# Atividade-03.net
KiCad netlist of a schematic drawn in EAGLE
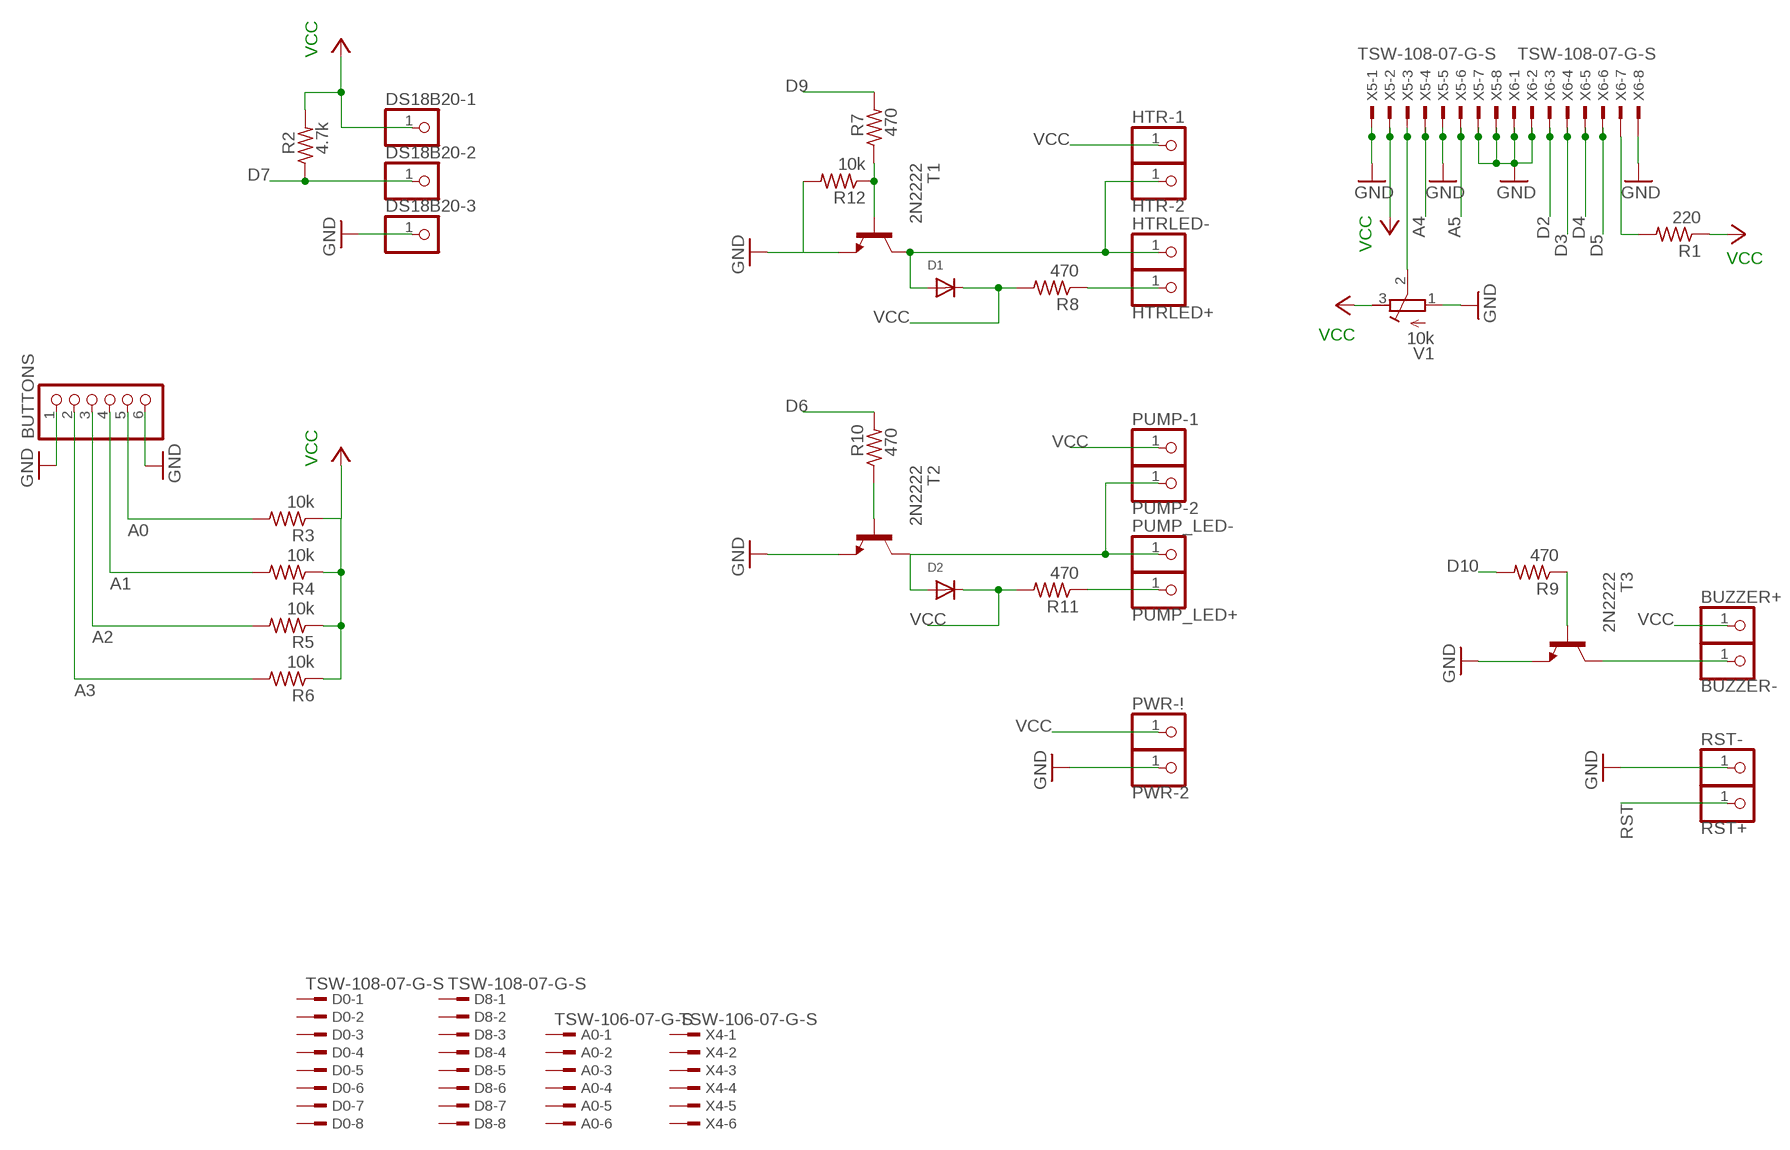
[diagram p0: schematic, sheet 1]

(export (version "E")
  (design (tool "Eeschema 10.0.6"))
  (components
    (comp (ref "A0")
      (value "TSW-106-07-G-S")
      (footprint "eagle-import:TSW-106-XX-G-S")
      (fields (field (name "MF") "Samtec Inc."))
      (libsource (lib "eagle-import") (part "TSW-106--G-S07"))
    )
    (comp (ref "BUTTONS")
      (value "PINHD-1X6")
      (footprint "eagle-import:1X06")
      (libsource (lib "eagle-import") (part "PINHD-1X6"))
    )
    (comp (ref "BUZZER+")
      (value "PINHD-1X1")
      (footprint "eagle-import:1X01")
      (libsource (lib "eagle-import") (part "PINHD-1X1"))
    )
    (comp (ref "BUZZER-")
      (value "PINHD-1X1")
      (footprint "eagle-import:1X01")
      (libsource (lib "eagle-import") (part "PINHD-1X1"))
    )
    (comp (ref "D0")
      (value "TSW-108-07-G-S")
      (footprint "eagle-import:TSW-108-XX-G-S")
      (fields (field (name "MF") "Samtec Inc."))
      (libsource (lib "eagle-import") (part "TSW-108--G-S07"))
    )
    (comp (ref "D1")
      (value "DIODEDO-1N4148")
      (footprint "eagle-import:DO-1N4148")
      (libsource (lib "eagle-import") (part "DIODEDO-1N4148"))
    )
    (comp (ref "D2")
      (value "DIODEDO-1N4148")
      (footprint "eagle-import:DO-1N4148")
      (libsource (lib "eagle-import") (part "DIODEDO-1N4148"))
    )
    (comp (ref "D8")
      (value "TSW-108-07-G-S")
      (footprint "eagle-import:TSW-108-XX-G-S")
      (fields (field (name "MF") "Samtec Inc."))
      (libsource (lib "eagle-import") (part "TSW-108--G-S07"))
    )
    (comp (ref "DS18B20-1")
      (value "PINHD-1X1")
      (footprint "eagle-import:1X01")
      (libsource (lib "eagle-import") (part "PINHD-1X1"))
    )
    (comp (ref "DS18B20-2")
      (value "PINHD-1X1")
      (footprint "eagle-import:1X01")
      (libsource (lib "eagle-import") (part "PINHD-1X1"))
    )
    (comp (ref "DS18B20-3")
      (value "PINHD-1X1")
      (footprint "eagle-import:1X01")
      (libsource (lib "eagle-import") (part "PINHD-1X1"))
    )
    (comp (ref "HTR-1")
      (value "PINHD-1X1")
      (footprint "eagle-import:1X01")
      (libsource (lib "eagle-import") (part "PINHD-1X1"))
    )
    (comp (ref "HTR-2")
      (value "PINHD-1X1")
      (footprint "eagle-import:1X01")
      (libsource (lib "eagle-import") (part "PINHD-1X1"))
    )
    (comp (ref "HTRLED+")
      (value "PINHD-1X1")
      (footprint "eagle-import:1X01")
      (libsource (lib "eagle-import") (part "PINHD-1X1"))
    )
    (comp (ref "HTRLED-")
      (value "PINHD-1X1")
      (footprint "eagle-import:1X01")
      (libsource (lib "eagle-import") (part "PINHD-1X1"))
    )
    (comp (ref "PUMP-1")
      (value "PINHD-1X1")
      (footprint "eagle-import:1X01")
      (libsource (lib "eagle-import") (part "PINHD-1X1"))
    )
    (comp (ref "PUMP-2")
      (value "PINHD-1X1")
      (footprint "eagle-import:1X01")
      (libsource (lib "eagle-import") (part "PINHD-1X1"))
    )
    (comp (ref "PUMP_LED+")
      (value "PINHD-1X1")
      (footprint "eagle-import:1X01")
      (libsource (lib "eagle-import") (part "PINHD-1X1"))
    )
    (comp (ref "PUMP_LED-")
      (value "PINHD-1X1")
      (footprint "eagle-import:1X01")
      (libsource (lib "eagle-import") (part "PINHD-1X1"))
    )
    (comp (ref "PWR-!")
      (value "PINHD-1X1")
      (footprint "eagle-import:1X01")
      (libsource (lib "eagle-import") (part "PINHD-1X1"))
    )
    (comp (ref "PWR-2")
      (value "PINHD-1X1")
      (footprint "eagle-import:1X01")
      (libsource (lib "eagle-import") (part "PINHD-1X1"))
    )
    (comp (ref "R1")
      (value "220")
      (footprint "eagle-import:0207_7")
      (libsource (lib "eagle-import") (part "R-US_0207/7"))
    )
    (comp (ref "R2")
      (value "4.7k")
      (footprint "eagle-import:0207_7")
      (libsource (lib "eagle-import") (part "R-US_0207/7"))
    )
    (comp (ref "R3")
      (value "10k")
      (footprint "eagle-import:0207_7")
      (libsource (lib "eagle-import") (part "R-US_0207/7"))
    )
    (comp (ref "R4")
      (value "10k")
      (footprint "eagle-import:0207_7")
      (libsource (lib "eagle-import") (part "R-US_0207/7"))
    )
    (comp (ref "R5")
      (value "10k")
      (footprint "eagle-import:0207_7")
      (libsource (lib "eagle-import") (part "R-US_0207/7"))
    )
    (comp (ref "R6")
      (value "10k")
      (footprint "eagle-import:0207_7")
      (libsource (lib "eagle-import") (part "R-US_0207/7"))
    )
    (comp (ref "R7")
      (value "470")
      (footprint "eagle-import:0207_7")
      (libsource (lib "eagle-import") (part "R-US_0207/7"))
    )
    (comp (ref "R8")
      (value "470")
      (footprint "eagle-import:0207_7")
      (libsource (lib "eagle-import") (part "R-US_0207/7"))
    )
    (comp (ref "R9")
      (value "470")
      (footprint "eagle-import:0207_7")
      (libsource (lib "eagle-import") (part "R-US_0207/7"))
    )
    (comp (ref "R10")
      (value "470")
      (footprint "eagle-import:0207_7")
      (libsource (lib "eagle-import") (part "R-US_0207/7"))
    )
    (comp (ref "R11")
      (value "470")
      (footprint "eagle-import:0207_7")
      (libsource (lib "eagle-import") (part "R-US_0207/7"))
    )
    (comp (ref "R12")
      (value "10k")
      (footprint "eagle-import:0207_7")
      (libsource (lib "eagle-import") (part "R-US_0207/7"))
    )
    (comp (ref "RST+")
      (value "PINHD-1X1")
      (footprint "eagle-import:1X01")
      (libsource (lib "eagle-import") (part "PINHD-1X1"))
    )
    (comp (ref "RST-")
      (value "PINHD-1X1")
      (footprint "eagle-import:1X01")
      (libsource (lib "eagle-import") (part "PINHD-1X1"))
    )
    (comp (ref "T1")
      (value "2N2222")
      (footprint "eagle-import:TO92-EBC-OVAL")
      (libsource (lib "eagle-import") (part "2N2222"))
    )
    (comp (ref "T2")
      (value "2N2222")
      (footprint "eagle-import:TO92-EBC-OVAL")
      (libsource (lib "eagle-import") (part "2N2222"))
    )
    (comp (ref "T3")
      (value "2N2222")
      (footprint "eagle-import:TO92-EBC-OVAL")
      (libsource (lib "eagle-import") (part "2N2222"))
    )
    (comp (ref "V1")
      (value "10k")
      (footprint "eagle-import:RTRIM5W")
      (libsource (lib "eagle-import") (part "R-TRIMM5W"))
    )
    (comp (ref "X4")
      (value "TSW-106-07-G-S")
      (footprint "eagle-import:TSW-106-XX-G-S")
      (fields (field (name "MF") "Samtec Inc."))
      (libsource (lib "eagle-import") (part "TSW-106--G-S07"))
    )
    (comp (ref "X5")
      (value "TSW-108-07-G-S")
      (footprint "eagle-import:TSW-108-XX-G-S")
      (fields (field (name "MF") "Samtec Inc."))
      (libsource (lib "eagle-import") (part "TSW-108--G-S07"))
    )
    (comp (ref "X6")
      (value "TSW-108-07-G-S")
      (footprint "eagle-import:TSW-108-XX-G-S")
      (fields (field (name "MF") "Samtec Inc."))
      (libsource (lib "eagle-import") (part "TSW-108--G-S07"))
    )
  )
  (nets
    (net (code "1") (name "/A0") (class "Default")
      (node (ref "BUTTONS") (pin "5") (pinfunction "5_5") (pintype "passive"))
      (node (ref "R3") (pin "2") (pinfunction "2_2") (pintype "passive"))
    )
    (net (code "2") (name "/A1") (class "Default")
      (node (ref "BUTTONS") (pin "4") (pinfunction "4_4") (pintype "passive"))
      (node (ref "R4") (pin "2") (pinfunction "2_2") (pintype "passive"))
    )
    (net (code "3") (name "/A2") (class "Default")
      (node (ref "BUTTONS") (pin "3") (pinfunction "3_3") (pintype "passive"))
      (node (ref "R5") (pin "2") (pinfunction "2_2") (pintype "passive"))
    )
    (net (code "4") (name "/A3") (class "Default")
      (node (ref "BUTTONS") (pin "2") (pinfunction "2_2") (pintype "passive"))
      (node (ref "R6") (pin "2") (pinfunction "2_2") (pintype "passive"))
    )
    (net (code "5") (name "/A4") (class "Default")
      (node (ref "X5") (pin "4") (pinfunction "1_4") (pintype "passive"))
    )
    (net (code "6") (name "/A5") (class "Default")
      (node (ref "X5") (pin "6") (pinfunction "1_6") (pintype "passive"))
    )
    (net (code "7") (name "/D2") (class "Default")
      (node (ref "X6") (pin "3") (pinfunction "1_3") (pintype "passive"))
    )
    (net (code "8") (name "/D3") (class "Default")
      (node (ref "X6") (pin "4") (pinfunction "1_4") (pintype "passive"))
    )
    (net (code "9") (name "/D4") (class "Default")
      (node (ref "X6") (pin "5") (pinfunction "1_5") (pintype "passive"))
    )
    (net (code "10") (name "/D5") (class "Default")
      (node (ref "X6") (pin "6") (pinfunction "1_6") (pintype "passive"))
    )
    (net (code "11") (name "/D6") (class "Default")
      (node (ref "R10") (pin "2") (pinfunction "2_2") (pintype "passive"))
    )
    (net (code "12") (name "/D7") (class "Default")
      (node (ref "DS18B20-2") (pin "1") (pinfunction "1_1") (pintype "passive"))
      (node (ref "R2") (pin "1") (pinfunction "1_1") (pintype "passive"))
    )
    (net (code "13") (name "/D9") (class "Default")
      (node (ref "R7") (pin "2") (pinfunction "2_2") (pintype "passive"))
    )
    (net (code "14") (name "/D10") (class "Default")
      (node (ref "R9") (pin "2") (pinfunction "2_2") (pintype "passive"))
    )
    (net (code "15") (name "/N$3") (class "Default")
      (node (ref "D1") (pin "A") (pinfunction "A_A") (pintype "passive"))
      (node (ref "D2") (pin "A") (pinfunction "A_A") (pintype "passive"))
      (node (ref "HTR-2") (pin "1") (pinfunction "1_1") (pintype "passive"))
      (node (ref "HTRLED-") (pin "1") (pinfunction "1_1") (pintype "passive"))
      (node (ref "PUMP-2") (pin "1") (pinfunction "1_1") (pintype "passive"))
      (node (ref "PUMP_LED-") (pin "1") (pinfunction "1_1") (pintype "passive"))
      (node (ref "T1") (pin "C") (pinfunction "C_C") (pintype "passive"))
      (node (ref "T2") (pin "C") (pinfunction "C_C") (pintype "passive"))
    )
    (net (code "16") (name "/N$5") (class "Default")
      (node (ref "HTRLED+") (pin "1") (pinfunction "1_1") (pintype "passive"))
      (node (ref "PUMP_LED+") (pin "1") (pinfunction "1_1") (pintype "passive"))
      (node (ref "R11") (pin "1") (pinfunction "1_1") (pintype "passive"))
      (node (ref "R8") (pin "1") (pinfunction "1_1") (pintype "passive"))
    )
    (net (code "17") (name "/RST") (class "Default")
      (node (ref "RST+") (pin "1") (pinfunction "1_1") (pintype "passive"))
    )
    (net (code "18") (name "GND") (class "Default")
      (node (ref "BUTTONS") (pin "1") (pinfunction "1_1") (pintype "passive"))
      (node (ref "BUTTONS") (pin "6") (pinfunction "6_6") (pintype "passive"))
      (node (ref "DS18B20-3") (pin "1") (pinfunction "1_1") (pintype "passive"))
      (node (ref "PWR-2") (pin "1") (pinfunction "1_1") (pintype "passive"))
      (node (ref "R12") (pin "2") (pinfunction "2_2") (pintype "passive"))
      (node (ref "RST-") (pin "1") (pinfunction "1_1") (pintype "passive"))
      (node (ref "T1") (pin "E") (pinfunction "E_E") (pintype "passive"))
      (node (ref "T2") (pin "E") (pinfunction "E_E") (pintype "passive"))
      (node (ref "T3") (pin "E") (pinfunction "E_E") (pintype "passive"))
      (node (ref "V1") (pin "1") (pinfunction "A_1") (pintype "passive"))
      (node (ref "X5") (pin "1") (pinfunction "1_1") (pintype "passive"))
      (node (ref "X5") (pin "5") (pinfunction "1_5") (pintype "passive"))
      (node (ref "X5") (pin "7") (pinfunction "1_7") (pintype "passive"))
      (node (ref "X5") (pin "8") (pinfunction "1_8") (pintype "passive"))
      (node (ref "X6") (pin "1") (pinfunction "1_1") (pintype "passive"))
      (node (ref "X6") (pin "2") (pinfunction "1_2") (pintype "passive"))
      (node (ref "X6") (pin "8") (pinfunction "1_8") (pintype "passive"))
    )
    (net (code "19") (name "Net-(BUZZER--Pad1)") (class "Default")
      (node (ref "BUZZER-") (pin "1") (pinfunction "1_1") (pintype "passive"))
      (node (ref "T3") (pin "C") (pinfunction "C_C") (pintype "passive"))
    )
    (net (code "20") (name "Net-(R9-Pad1)") (class "Default")
      (node (ref "R9") (pin "1") (pinfunction "1_1") (pintype "passive"))
      (node (ref "T3") (pin "B") (pinfunction "B_B") (pintype "passive"))
    )
    (net (code "21") (name "Net-(R10-Pad1)") (class "Default")
      (node (ref "R10") (pin "1") (pinfunction "1_1") (pintype "passive"))
      (node (ref "T2") (pin "B") (pinfunction "B_B") (pintype "passive"))
    )
    (net (code "22") (name "Net-(R12-Pad1)") (class "Default")
      (node (ref "R12") (pin "1") (pinfunction "1_1") (pintype "passive"))
      (node (ref "R7") (pin "1") (pinfunction "1_1") (pintype "passive"))
      (node (ref "T1") (pin "B") (pinfunction "B_B") (pintype "passive"))
    )
    (net (code "23") (name "Net-(V1-S)") (class "Default")
      (node (ref "V1") (pin "2") (pinfunction "S_2") (pintype "passive"))
      (node (ref "X5") (pin "3") (pinfunction "1_3") (pintype "passive"))
    )
    (net (code "24") (name "Net-(X6G-1)") (class "Default")
      (node (ref "R1") (pin "2") (pinfunction "2_2") (pintype "passive"))
      (node (ref "X6") (pin "7") (pinfunction "1_7") (pintype "passive"))
    )
    (net (code "25") (name "VCC") (class "Default")
      (node (ref "BUZZER+") (pin "1") (pinfunction "1_1") (pintype "passive"))
      (node (ref "D1") (pin "C") (pinfunction "C_C") (pintype "passive"))
      (node (ref "D2") (pin "C") (pinfunction "C_C") (pintype "passive"))
      (node (ref "DS18B20-1") (pin "1") (pinfunction "1_1") (pintype "passive"))
      (node (ref "HTR-1") (pin "1") (pinfunction "1_1") (pintype "passive"))
      (node (ref "PUMP-1") (pin "1") (pinfunction "1_1") (pintype "passive"))
      (node (ref "PWR-!") (pin "1") (pinfunction "1_1") (pintype "passive"))
      (node (ref "R1") (pin "1") (pinfunction "1_1") (pintype "passive"))
      (node (ref "R11") (pin "2") (pinfunction "2_2") (pintype "passive"))
      (node (ref "R2") (pin "2") (pinfunction "2_2") (pintype "passive"))
      (node (ref "R3") (pin "1") (pinfunction "1_1") (pintype "passive"))
      (node (ref "R4") (pin "1") (pinfunction "1_1") (pintype "passive"))
      (node (ref "R5") (pin "1") (pinfunction "1_1") (pintype "passive"))
      (node (ref "R6") (pin "1") (pinfunction "1_1") (pintype "passive"))
      (node (ref "R8") (pin "2") (pinfunction "2_2") (pintype "passive"))
      (node (ref "V1") (pin "3") (pinfunction "E_3") (pintype "passive"))
      (node (ref "X5") (pin "2") (pinfunction "1_2") (pintype "passive"))
    )
    (net (code "26") (name "unconnected-(A0-Pad1)") (class "Default")
      (node (ref "A0") (pin "1") (pinfunction "1_1") (pintype "passive"))
    )
    (net (code "27") (name "unconnected-(A0B-1-Pad2)") (class "Default")
      (node (ref "A0") (pin "2") (pinfunction "1_2") (pintype "passive"))
    )
    (net (code "28") (name "unconnected-(A0C-1-Pad3)") (class "Default")
      (node (ref "A0") (pin "3") (pinfunction "1_3") (pintype "passive"))
    )
    (net (code "29") (name "unconnected-(A0D-1-Pad4)") (class "Default")
      (node (ref "A0") (pin "4") (pinfunction "1_4") (pintype "passive"))
    )
    (net (code "30") (name "unconnected-(A0E-1-Pad5)") (class "Default")
      (node (ref "A0") (pin "5") (pinfunction "1_5") (pintype "passive"))
    )
    (net (code "31") (name "unconnected-(A0F-1-Pad6)") (class "Default")
      (node (ref "A0") (pin "6") (pinfunction "1_6") (pintype "passive"))
    )
    (net (code "32") (name "unconnected-(D0-Pad1)") (class "Default")
      (node (ref "D0") (pin "1") (pinfunction "1_1") (pintype "passive"))
    )
    (net (code "33") (name "unconnected-(D0B-1-Pad2)") (class "Default")
      (node (ref "D0") (pin "2") (pinfunction "1_2") (pintype "passive"))
    )
    (net (code "34") (name "unconnected-(D0C-1-Pad3)") (class "Default")
      (node (ref "D0") (pin "3") (pinfunction "1_3") (pintype "passive"))
    )
    (net (code "35") (name "unconnected-(D0D-1-Pad4)") (class "Default")
      (node (ref "D0") (pin "4") (pinfunction "1_4") (pintype "passive"))
    )
    (net (code "36") (name "unconnected-(D0E-1-Pad5)") (class "Default")
      (node (ref "D0") (pin "5") (pinfunction "1_5") (pintype "passive"))
    )
    (net (code "37") (name "unconnected-(D0F-1-Pad6)") (class "Default")
      (node (ref "D0") (pin "6") (pinfunction "1_6") (pintype "passive"))
    )
    (net (code "38") (name "unconnected-(D0G-1-Pad7)") (class "Default")
      (node (ref "D0") (pin "7") (pinfunction "1_7") (pintype "passive"))
    )
    (net (code "39") (name "unconnected-(D0H-1-Pad8)") (class "Default")
      (node (ref "D0") (pin "8") (pinfunction "1_8") (pintype "passive"))
    )
    (net (code "40") (name "unconnected-(D8-Pad1)") (class "Default")
      (node (ref "D8") (pin "1") (pinfunction "1_1") (pintype "passive"))
    )
    (net (code "41") (name "unconnected-(D8B-1-Pad2)") (class "Default")
      (node (ref "D8") (pin "2") (pinfunction "1_2") (pintype "passive"))
    )
    (net (code "42") (name "unconnected-(D8C-1-Pad3)") (class "Default")
      (node (ref "D8") (pin "3") (pinfunction "1_3") (pintype "passive"))
    )
    (net (code "43") (name "unconnected-(D8D-1-Pad4)") (class "Default")
      (node (ref "D8") (pin "4") (pinfunction "1_4") (pintype "passive"))
    )
    (net (code "44") (name "unconnected-(D8E-1-Pad5)") (class "Default")
      (node (ref "D8") (pin "5") (pinfunction "1_5") (pintype "passive"))
    )
    (net (code "45") (name "unconnected-(D8F-1-Pad6)") (class "Default")
      (node (ref "D8") (pin "6") (pinfunction "1_6") (pintype "passive"))
    )
    (net (code "46") (name "unconnected-(D8G-1-Pad7)") (class "Default")
      (node (ref "D8") (pin "7") (pinfunction "1_7") (pintype "passive"))
    )
    (net (code "47") (name "unconnected-(D8H-1-Pad8)") (class "Default")
      (node (ref "D8") (pin "8") (pinfunction "1_8") (pintype "passive"))
    )
    (net (code "48") (name "unconnected-(X4-Pad1)") (class "Default")
      (node (ref "X4") (pin "1") (pinfunction "1_1") (pintype "passive"))
    )
    (net (code "49") (name "unconnected-(X4B-1-Pad2)") (class "Default")
      (node (ref "X4") (pin "2") (pinfunction "1_2") (pintype "passive"))
    )
    (net (code "50") (name "unconnected-(X4C-1-Pad3)") (class "Default")
      (node (ref "X4") (pin "3") (pinfunction "1_3") (pintype "passive"))
    )
    (net (code "51") (name "unconnected-(X4D-1-Pad4)") (class "Default")
      (node (ref "X4") (pin "4") (pinfunction "1_4") (pintype "passive"))
    )
    (net (code "52") (name "unconnected-(X4E-1-Pad5)") (class "Default")
      (node (ref "X4") (pin "5") (pinfunction "1_5") (pintype "passive"))
    )
    (net (code "53") (name "unconnected-(X4F-1-Pad6)") (class "Default")
      (node (ref "X4") (pin "6") (pinfunction "1_6") (pintype "passive"))
    )
  )
)
